# lin_node.net
KiCad netlist of a schematic drawn in EAGLE
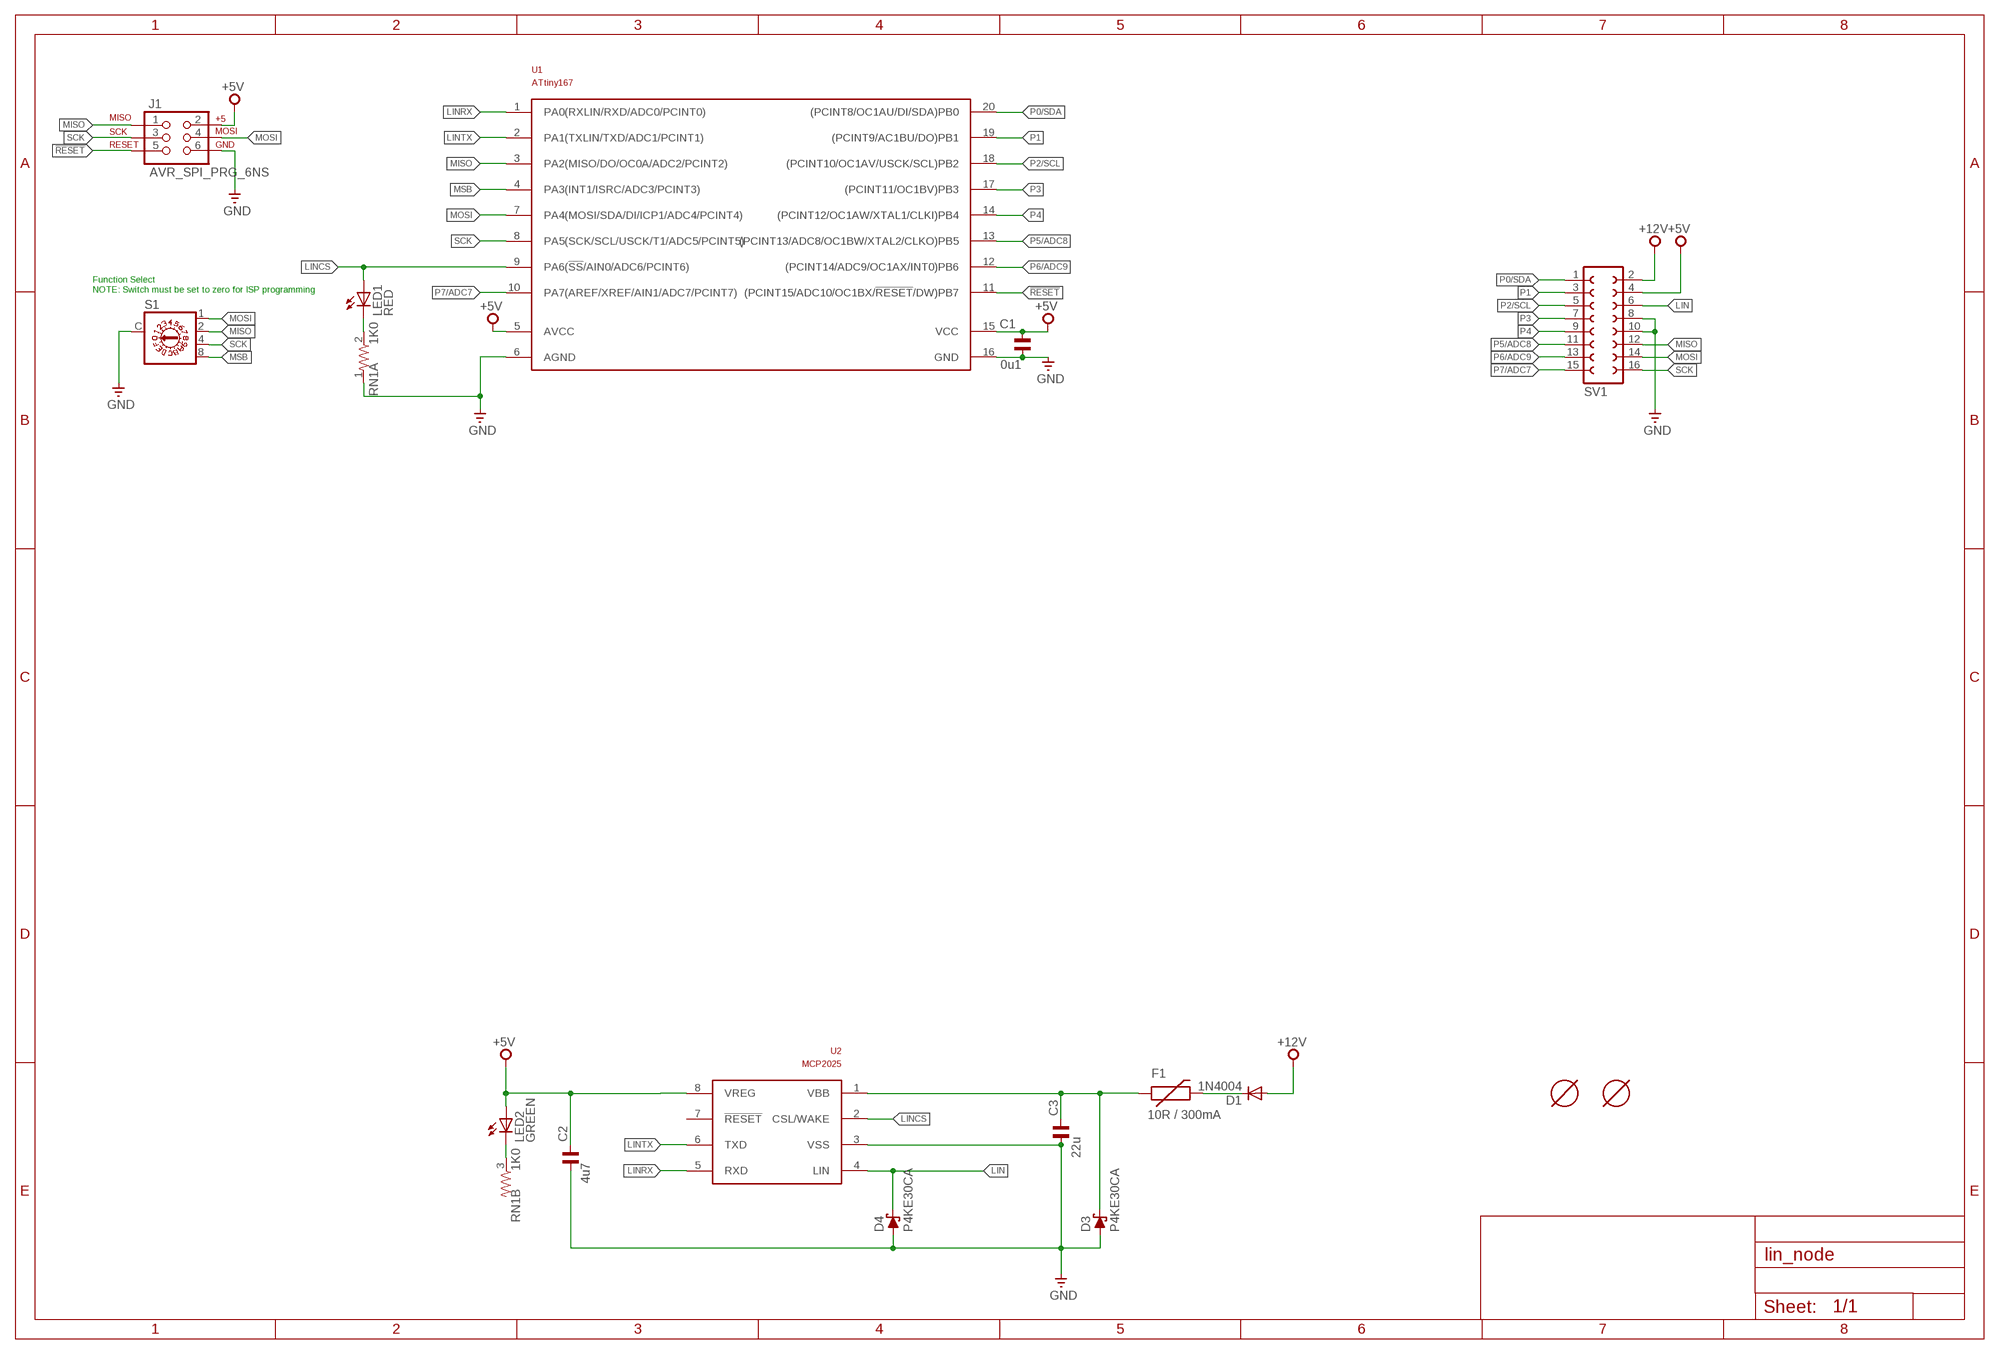
[diagram p0: schematic, sheet 1]

(export (version "E")
  (design (tool "Eeschema 10.0.6"))
  (components
    (comp (ref "C1")
      (value "0u1")
      (footprint "eagle-import:C025-024X044")
      (fields (field (name "PARTNO") "FK28X7R1H104K"))
      (libsource (lib "eagle-import") (part "C-EU025-024X044"))
    )
    (comp (ref "C2")
      (value "4u7")
      (footprint "eagle-import:C050-024X044")
      (fields (field (name "PARTNO") "FK28X5R0J475K"))
      (libsource (lib "eagle-import") (part "C-EU050-024X044"))
    )
    (comp (ref "C3")
      (value "22u")
      (footprint "eagle-import:C050-024X044")
      (fields (field (name "PARTNO") "FK22X5R1E226M"))
      (libsource (lib "eagle-import") (part "C-EU050-024X044"))
    )
    (comp (ref "D1")
      (value "1N4004")
      (footprint "eagle-import:DO41-10")
      (fields (field (name "PARTNO") "1N4004-TP"))
      (libsource (lib "eagle-import") (part "1N4004"))
    )
    (comp (ref "D3")
      (value "P4KE30CA")
      (footprint "eagle-import:DO41-10")
      (libsource (lib "eagle-import") (part "P4KEXX"))
    )
    (comp (ref "D4")
      (value "P4KE30CA")
      (footprint "eagle-import:DO41-10")
      (libsource (lib "eagle-import") (part "P4KEXX"))
    )
    (comp (ref "F1")
      (value "10R / 300mA")
      (footprint "eagle-import:PTC")
      (fields (field (name "PARTNO") "600R150-RBZR"))
      (libsource (lib "eagle-import") (part "PTCPTH"))
    )
    (comp (ref "J1")
      (value "AVR_SPI_PRG_6NS")
      (footprint "eagle-import:2X3-NS")
      (libsource (lib "eagle-import") (part "AVR_SPI_PRG_6NS"))
    )
    (comp (ref "LED1")
      (value "RED")
      (footprint "eagle-import:LED3MM")
      (fields (field (name "PARTNO") "C4SMF-RJS-CT0W0BB2"))
      (libsource (lib "eagle-import") (part "LED3MM"))
    )
    (comp (ref "LED2")
      (value "GREEN")
      (footprint "eagle-import:LED3MM")
      (fields (field (name "PARTNO") "C4SMF-GJS-CV0Y0792"))
      (libsource (lib "eagle-import") (part "LED3MM"))
    )
    (comp (ref "RN1")
      (value "1K0")
      (footprint "eagle-import:SIL4")
      (fields (field (name "PARTNO") "4604X-101-103LF"))
      (libsource (lib "eagle-import") (part "GE03R"))
    )
    (comp (ref "S1")
      (value "P103")
      (footprint "eagle-import:P103")
      (fields (field (name "PARTNO") "SH-7050MC"))
      (libsource (lib "eagle-import") (part "P103"))
    )
    (comp (ref "SV1")
      (value "FE08-2")
      (footprint "eagle-import:FE08-2")
      (libsource (lib "eagle-import") (part "FE08-2"))
    )
    (comp (ref "U$1")
      (value "MOUNT-HOLE3.1MM")
      (footprint "eagle-import:MOUNT-HOLE3.1")
      (libsource (lib "eagle-import") (part "MOUNT-HOLE3.1MM"))
    )
    (comp (ref "U$2")
      (value "MOUNT-HOLE3.1MM")
      (footprint "eagle-import:MOUNT-HOLE3.1")
      (libsource (lib "eagle-import") (part "MOUNT-HOLE3.1MM"))
    )
    (comp (ref "U1")
      (value "ATtiny167")
      (footprint "eagle-import:SO20W")
      (fields (field (name "PARTNO") "ATTINY167-SU"))
      (libsource (lib "eagle-import") (part "ATTINY167"))
    )
    (comp (ref "U2")
      (value "MCP2025")
      (footprint "eagle-import:SO08")
      (fields (field (name "PARTNO") "MCP2025-500E/SN"))
      (libsource (lib "eagle-import") (part "MCP2025"))
    )
  )
  (nets
    (net (code "1") (name "+5V") (class "Default")
      (node (ref "C1") (pin "1") (pinfunction "1_1") (pintype "passive"))
      (node (ref "C2") (pin "1") (pinfunction "1_1") (pintype "passive"))
      (node (ref "J1") (pin "2") (pinfunction "2_2") (pintype "passive"))
      (node (ref "LED2") (pin "A") (pinfunction "A_A") (pintype "passive"))
      (node (ref "SV1") (pin "4") (pinfunction "4_4") (pintype "passive"))
      (node (ref "U1") (pin "15") (pinfunction "VCC_15") (pintype "power_in"))
      (node (ref "U1") (pin "5") (pinfunction "AVCC_5") (pintype "power_in"))
      (node (ref "U2") (pin "8") (pinfunction "VREG_8") (pintype "power_in"))
    )
    (net (code "2") (name "+12V") (class "Default")
      (node (ref "D1") (pin "A") (pinfunction "A_A") (pintype "passive"))
      (node (ref "SV1") (pin "2") (pinfunction "2_2") (pintype "passive"))
    )
    (net (code "3") (name "/~{RESET}") (class "Default")
      (node (ref "J1") (pin "5") (pinfunction "5_5") (pintype "passive"))
      (node (ref "U1") (pin "11") (pinfunction "(PCINT15/ADC10/OC1BX/~{RESET}/DW)PB7_11") (pintype "bidirectional"))
    )
    (net (code "4") (name "GND") (class "Default")
      (node (ref "C1") (pin "2") (pinfunction "2_2") (pintype "passive"))
      (node (ref "C2") (pin "2") (pinfunction "2_2") (pintype "passive"))
      (node (ref "C3") (pin "2") (pinfunction "2_2") (pintype "passive"))
      (node (ref "D3") (pin "A") (pinfunction "A_A") (pintype "passive"))
      (node (ref "D4") (pin "A") (pinfunction "A_A") (pintype "passive"))
      (node (ref "J1") (pin "6") (pinfunction "6_6") (pintype "passive"))
      (node (ref "RN1") (pin "1") (pinfunction "1_1") (pintype "passive"))
      (node (ref "S1") (pin "C") (pinfunction "C_C") (pintype "passive"))
      (node (ref "SV1") (pin "10") (pinfunction "10_10") (pintype "passive"))
      (node (ref "SV1") (pin "8") (pinfunction "8_8") (pintype "passive"))
      (node (ref "U1") (pin "16") (pinfunction "GND_16") (pintype "power_in"))
      (node (ref "U1") (pin "6") (pinfunction "AGND_6") (pintype "power_in"))
      (node (ref "U2") (pin "3") (pinfunction "VSS_3") (pintype "power_in"))
    )
    (net (code "5") (name "LIN") (class "Default")
      (node (ref "D4") (pin "C") (pinfunction "C_C") (pintype "passive"))
      (node (ref "SV1") (pin "6") (pinfunction "6_6") (pintype "passive"))
      (node (ref "U2") (pin "4") (pinfunction "LIN_4") (pintype "bidirectional"))
    )
    (net (code "6") (name "LINCS") (class "Default")
      (node (ref "LED1") (pin "A") (pinfunction "A_A") (pintype "passive"))
      (node (ref "U1") (pin "9") (pinfunction "PA6(~{SS}/AIN0/ADC6/PCINT6)_9") (pintype "bidirectional"))
      (node (ref "U2") (pin "2") (pinfunction "CSL/WAKE_2") (pintype "input"))
    )
    (net (code "7") (name "LINRX") (class "Default")
      (node (ref "U1") (pin "1") (pinfunction "PA0(RXLIN/RXD/ADC0/PCINT0)_1") (pintype "bidirectional"))
      (node (ref "U2") (pin "5") (pinfunction "RXD_5") (pintype "output"))
    )
    (net (code "8") (name "LINTX") (class "Default")
      (node (ref "U1") (pin "2") (pinfunction "PA1(TXLIN/TXD/ADC1/PCINT1)_2") (pintype "bidirectional"))
      (node (ref "U2") (pin "6") (pinfunction "TXD_6") (pintype "input"))
    )
    (net (code "9") (name "MISO") (class "Default")
      (node (ref "J1") (pin "1") (pinfunction "1_1") (pintype "passive"))
      (node (ref "S1") (pin "2") (pinfunction "2_2") (pintype "passive"))
      (node (ref "SV1") (pin "12") (pinfunction "12_12") (pintype "passive"))
      (node (ref "U1") (pin "3") (pinfunction "PA2(MISO/DO/OC0A/ADC2/PCINT2)_3") (pintype "bidirectional"))
    )
    (net (code "10") (name "MOSI") (class "Default")
      (node (ref "J1") (pin "4") (pinfunction "4_4") (pintype "passive"))
      (node (ref "S1") (pin "1") (pinfunction "1_1") (pintype "passive"))
      (node (ref "SV1") (pin "14") (pinfunction "14_14") (pintype "passive"))
      (node (ref "U1") (pin "7") (pinfunction "PA4(MOSI/SDA/DI/ICP1/ADC4/PCINT4)_7") (pintype "bidirectional"))
    )
    (net (code "11") (name "MSB") (class "Default")
      (node (ref "S1") (pin "8") (pinfunction "8_8") (pintype "passive"))
      (node (ref "U1") (pin "4") (pinfunction "PA3(INT1/ISRC/ADC3/PCINT3)_4") (pintype "bidirectional"))
    )
    (net (code "12") (name "Net-(F1-1)") (class "Default")
      (node (ref "C3") (pin "1") (pinfunction "1_1") (pintype "passive"))
      (node (ref "D3") (pin "C") (pinfunction "C_C") (pintype "passive"))
      (node (ref "F1") (pin "P$1") (pinfunction "1_P$1") (pintype "bidirectional"))
      (node (ref "U2") (pin "1") (pinfunction "VBB_1") (pintype "power_in"))
    )
    (net (code "13") (name "Net-(F1-2)") (class "Default")
      (node (ref "D1") (pin "C") (pinfunction "C_C") (pintype "passive"))
      (node (ref "F1") (pin "P$2") (pinfunction "2_P$2") (pintype "bidirectional"))
    )
    (net (code "14") (name "Net-(LED1-C)") (class "Default")
      (node (ref "LED1") (pin "K") (pinfunction "C_K") (pintype "passive"))
      (node (ref "RN1") (pin "2") (pinfunction "2_2") (pintype "passive"))
    )
    (net (code "15") (name "Net-(LED2-C)") (class "Default")
      (node (ref "LED2") (pin "K") (pinfunction "C_K") (pintype "passive"))
      (node (ref "RN1") (pin "3") (pinfunction "2_3") (pintype "passive"))
    )
    (net (code "16") (name "P0{slash}SDA") (class "Default")
      (node (ref "SV1") (pin "1") (pinfunction "1_1") (pintype "passive"))
      (node (ref "U1") (pin "20") (pinfunction "(PCINT8/OC1AU/DI/SDA)PB0_20") (pintype "bidirectional"))
    )
    (net (code "17") (name "P1") (class "Default")
      (node (ref "SV1") (pin "3") (pinfunction "3_3") (pintype "passive"))
      (node (ref "U1") (pin "19") (pinfunction "(PCINT9/AC1BU/DO)PB1_19") (pintype "bidirectional"))
    )
    (net (code "18") (name "P2{slash}SCL") (class "Default")
      (node (ref "SV1") (pin "5") (pinfunction "5_5") (pintype "passive"))
      (node (ref "U1") (pin "18") (pinfunction "(PCINT10/OC1AV/USCK/SCL)PB2_18") (pintype "bidirectional"))
    )
    (net (code "19") (name "P3") (class "Default")
      (node (ref "SV1") (pin "7") (pinfunction "7_7") (pintype "passive"))
      (node (ref "U1") (pin "17") (pinfunction "(PCINT11/OC1BV)PB3_17") (pintype "bidirectional"))
    )
    (net (code "20") (name "P4") (class "Default")
      (node (ref "SV1") (pin "9") (pinfunction "9_9") (pintype "passive"))
      (node (ref "U1") (pin "14") (pinfunction "(PCINT12/OC1AW/XTAL1/CLKI)PB4_14") (pintype "bidirectional"))
    )
    (net (code "21") (name "P5{slash}ADC8") (class "Default")
      (node (ref "SV1") (pin "11") (pinfunction "11_11") (pintype "passive"))
      (node (ref "U1") (pin "13") (pinfunction "(PCINT13/ADC8/OC1BW/XTAL2/CLKO)PB5_13") (pintype "bidirectional"))
    )
    (net (code "22") (name "P6{slash}ADC9") (class "Default")
      (node (ref "SV1") (pin "13") (pinfunction "13_13") (pintype "passive"))
      (node (ref "U1") (pin "12") (pinfunction "(PCINT14/ADC9/OC1AX/INT0)PB6_12") (pintype "bidirectional"))
    )
    (net (code "23") (name "P7{slash}ADC7") (class "Default")
      (node (ref "SV1") (pin "15") (pinfunction "15_15") (pintype "passive"))
      (node (ref "U1") (pin "10") (pinfunction "PA7(AREF/XREF/AIN1/ADC7/PCINT7)_10") (pintype "bidirectional"))
    )
    (net (code "24") (name "SCK") (class "Default")
      (node (ref "J1") (pin "3") (pinfunction "3_3") (pintype "passive"))
      (node (ref "S1") (pin "4") (pinfunction "4_4") (pintype "passive"))
      (node (ref "SV1") (pin "16") (pinfunction "16_16") (pintype "passive"))
      (node (ref "U1") (pin "8") (pinfunction "PA5(SCK/SCL/USCK/T1/ADC5/PCINT5)_8") (pintype "bidirectional"))
    )
    (net (code "25") (name "unconnected-(U2-~{RESET}-Pad7)") (class "Default")
      (node (ref "U2") (pin "7") (pinfunction "~{RESET}_7") (pintype "open_collector"))
    )
  )
)
